# Temp_sensor.net
KiCad netlist of a schematic drawn in Altium Designer
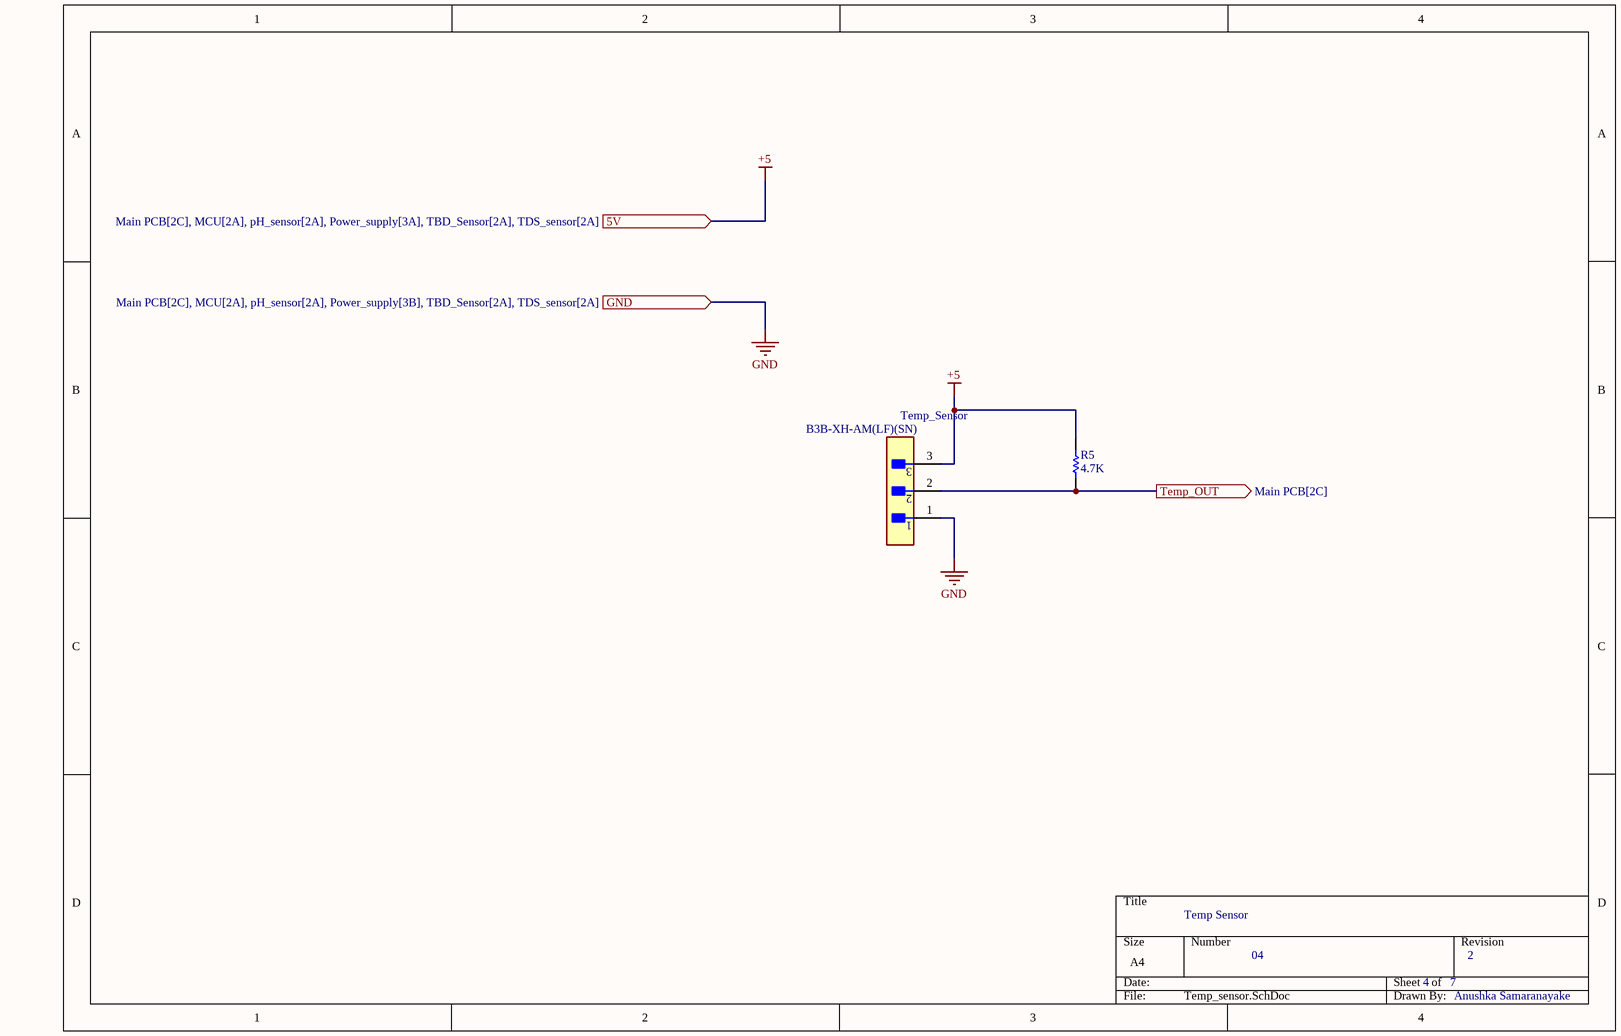
[diagram p0: Temp_sensor.SchDoc]

(export (version "E")
  (design (tool "Eeschema 10.0.6"))
  (components
    (comp (ref "R5")
      (value "4.7K")
      (footprint "RESC3216X70X50LL20T25")
      (fields (field (name "MANUFACTURER") "Panasonic") (field (name "PART NUMBER") "ERA8AEB103V"))
      (libsource (lib "Altium Content Vault") (part "RES"))
    )
    (comp (ref "Temp_Sensor")
      (value "B3B-XH-AM(LF)(SN)")
      (footprint "FP-B3B-XH-AM_LF_SN-MFG")
      (description "CONN HEADER VERT 3POS 2.5MM")
      (libsource (lib "Altium Content Vault") (part "0d3f023dd272f625e17a2be33dea85f"))
    )
  )
  (nets
    (net (code "1") (name "+5") (class "Default")
      (node (ref "R5") (pin "1") (pinfunction "1_1") (pintype "passive"))
      (node (ref "Temp_Sensor") (pin "3") (pinfunction "3_3") (pintype "passive"))
    )
    (net (code "2") (name "/Temp_OUT") (class "Default")
      (node (ref "R5") (pin "2") (pinfunction "2_2") (pintype "passive"))
      (node (ref "Temp_Sensor") (pin "2") (pinfunction "2_2") (pintype "passive"))
    )
    (net (code "3") (name "GND") (class "Default")
      (node (ref "Temp_Sensor") (pin "1") (pinfunction "1_1") (pintype "passive"))
    )
  )
)
